# Beacon_V1.net
KiCad netlist of a schematic drawn in Altium Designer
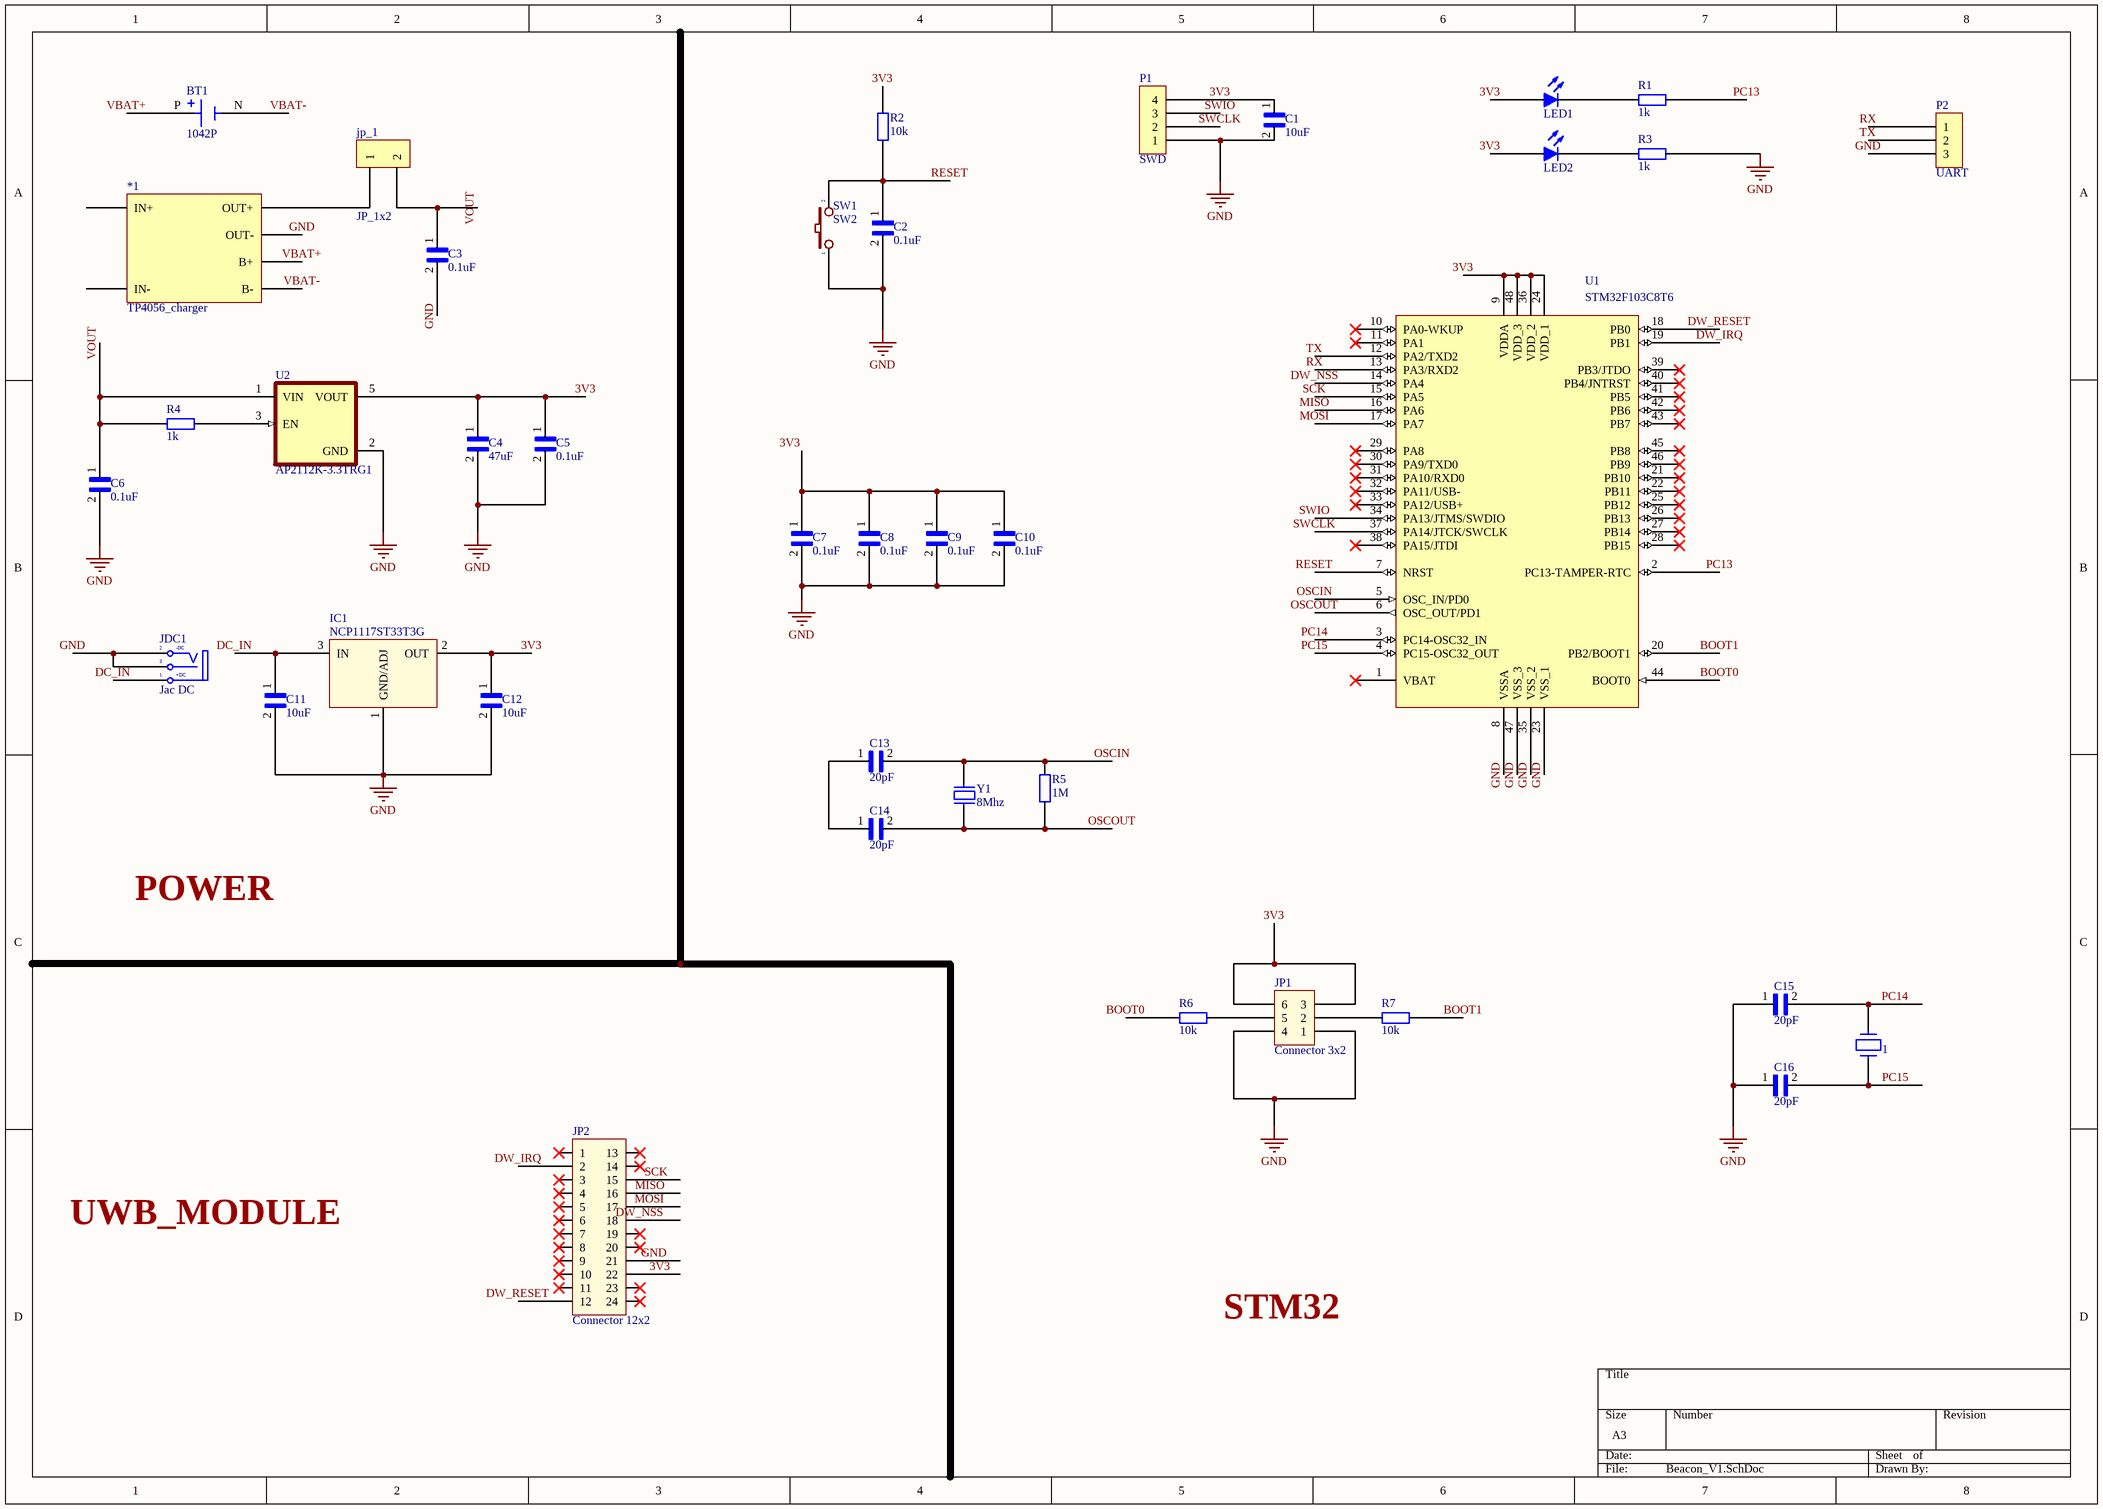
[diagram p0: Beacon_V1.SchDoc]

(export (version "E")
  (design (tool "Eeschema 10.0.6"))
  (components
    (comp (ref "*1")
      (value "TP4056_charger")
      (footprint "TP4056_charger")
      (libsource (lib "Target_tracking_20242v3") (part "TP4056_charger"))
    )
    (comp (ref "1")
      (value "ABS07")
      (footprint "ABS07")
      (description "SMD Quartz Crystal")
      (fields (field (name "CREATED BY") "Zion Blue") (field (name "PUBLISHER") "Cynetik Group"))
      (libsource (lib "Cty1") (part "ABS07"))
    )
    (comp (ref "BT1")
      (value "1042P")
      (footprint "BAT_1042P")
      (description "SMT Polarized Battery Holder for 18650 Battery ¦ Keystone Electronics 1042P")
      (fields (field (name "MF") "Keystone Electronics"))
      (libsource (lib "Project_LoRa") (part "1042P"))
    )
    (comp (ref "C1")
      (value "10uF")
      (footprint "Capacitor_0805")
      (description "Capacitor; Ceramic; Cap; .220uF; Tol 10%; SMT; Vol-Rtg 50V; X7R; Tape And Reel")
      (libsource (lib "") (part "Capacitor_0805_1"))
    )
    (comp (ref "C2")
      (value "0.1uF")
      (footprint "Capacitor_0805")
      (description "Capacitor; Ceramic; Cap; .220uF; Tol 10%; SMT; Vol-Rtg 50V; X7R; Tape And Reel")
      (libsource (lib "") (part "Capacitor_0805_1"))
    )
    (comp (ref "C3")
      (value "0.1uF")
      (footprint "Capacitor_0805")
      (description "Capacitor; Ceramic; Cap; .220uF; Tol 10%; SMT; Vol-Rtg 50V; X7R; Tape And Reel")
      (libsource (lib "") (part "Capacitor_0805_1"))
    )
    (comp (ref "C4")
      (value "47uF")
      (footprint "Capacitor_0805")
      (description "Capacitor; Ceramic; Cap; .220uF; Tol 10%; SMT; Vol-Rtg 50V; X7R; Tape And Reel")
      (libsource (lib "") (part "Capacitor_0805_1"))
    )
    (comp (ref "C5")
      (value "0.1uF")
      (footprint "Capacitor_0805")
      (description "Capacitor; Ceramic; Cap; .220uF; Tol 10%; SMT; Vol-Rtg 50V; X7R; Tape And Reel")
      (libsource (lib "") (part "Capacitor_0805_1"))
    )
    (comp (ref "C6")
      (value "0.1uF")
      (footprint "Capacitor_0805")
      (description "Capacitor; Ceramic; Cap; .220uF; Tol 10%; SMT; Vol-Rtg 50V; X7R; Tape And Reel")
      (libsource (lib "") (part "Capacitor_0805_1"))
    )
    (comp (ref "C7")
      (value "0.1uF")
      (footprint "Capacitor_0805")
      (description "Capacitor; Ceramic; Cap; .220uF; Tol 10%; SMT; Vol-Rtg 50V; X7R; Tape And Reel")
      (libsource (lib "") (part "Capacitor_0805_1"))
    )
    (comp (ref "C8")
      (value "0.1uF")
      (footprint "Capacitor_0805")
      (description "Capacitor; Ceramic; Cap; .220uF; Tol 10%; SMT; Vol-Rtg 50V; X7R; Tape And Reel")
      (libsource (lib "") (part "Capacitor_0805_1"))
    )
    (comp (ref "C9")
      (value "0.1uF")
      (footprint "Capacitor_0805")
      (description "Capacitor; Ceramic; Cap; .220uF; Tol 10%; SMT; Vol-Rtg 50V; X7R; Tape And Reel")
      (libsource (lib "") (part "Capacitor_0805_1"))
    )
    (comp (ref "C10")
      (value "0.1uF")
      (footprint "Capacitor_0805")
      (description "Capacitor; Ceramic; Cap; .220uF; Tol 10%; SMT; Vol-Rtg 50V; X7R; Tape And Reel")
      (libsource (lib "") (part "Capacitor_0805_1"))
    )
    (comp (ref "C11")
      (value "10uF")
      (footprint "Capacitor_0805")
      (description "Capacitor; Ceramic; Cap; .220uF; Tol 10%; SMT; Vol-Rtg 50V; X7R; Tape And Reel")
      (libsource (lib "") (part "Capacitor_0805_1"))
    )
    (comp (ref "C12")
      (value "10uF")
      (footprint "Capacitor_0805")
      (description "Capacitor; Ceramic; Cap; .220uF; Tol 10%; SMT; Vol-Rtg 50V; X7R; Tape And Reel")
      (libsource (lib "") (part "Capacitor_0805_1"))
    )
    (comp (ref "C13")
      (value "20pF")
      (footprint "Capacitor_0805")
      (description "Capacitor; Ceramic; Cap; .220uF; Tol 10%; SMT; Vol-Rtg 50V; X7R; Tape And Reel")
      (libsource (lib "Target_tracking_20242v3") (part "Capacitor_0805"))
    )
    (comp (ref "C14")
      (value "20pF")
      (footprint "Capacitor_0805")
      (description "Capacitor; Ceramic; Cap; .220uF; Tol 10%; SMT; Vol-Rtg 50V; X7R; Tape And Reel")
      (libsource (lib "Target_tracking_20242v3") (part "Capacitor_0805"))
    )
    (comp (ref "C15")
      (value "20pF")
      (footprint "Capacitor_0805")
      (description "Capacitor; Ceramic; Cap; .220uF; Tol 10%; SMT; Vol-Rtg 50V; X7R; Tape And Reel")
      (libsource (lib "Target_tracking_20242v3") (part "Capacitor_0805"))
    )
    (comp (ref "C16")
      (value "20pF")
      (footprint "Capacitor_0805")
      (description "Capacitor; Ceramic; Cap; .220uF; Tol 10%; SMT; Vol-Rtg 50V; X7R; Tape And Reel")
      (libsource (lib "Target_tracking_20242v3") (part "Capacitor_0805"))
    )
    (comp (ref "IC1")
      (value "NCP1117ST33T3G")
      (footprint "SOT223-3_ONS")
      (description "SOT223")
      (libsource (lib "SCH_MyLib_0") (part "NCP1117ST33T3G"))
    )
    (comp (ref "JDC1")
      (value "Jac DC")
      (footprint "DC-IN")
      (description "Jac DC input")
      (libsource (lib "syhaunguyen") (part "DCIN"))
    )
    (comp (ref "JP1") (value "Connector 3x2") (footprint "JP3x2") (libsource (lib "Cty1") (part "JP3x2")))
    (comp (ref "JP2")
      (value "Connector 12x2")
      (footprint "JP12X2_1")
      (libsource (lib "Cty1") (part "JP12x2"))
    )
    (comp (ref "jp_1")
      (value "JP_1x2")
      (footprint "JP_1x2")
      (libsource (lib "Target_tracking_20242v3") (part "JP_1x2"))
    )
    (comp (ref "LED1")
      (value "Led")
      (footprint "Led 0805 Blue")
      (description "Typical LED")
      (libsource (lib "Project_LoRa") (part "Led"))
    )
    (comp (ref "LED2")
      (value "Led")
      (footprint "Led 0805 Blue")
      (description "Typical LED")
      (libsource (lib "Project_LoRa") (part "Led"))
    )
    (comp (ref "P1")
      (value "SWD")
      (footprint "HDR/Header/4/BOX")
      (description "Header, 4-Pin")
      (libsource (lib "Project_LoRa") (part "Header 4_1"))
    )
    (comp (ref "P2")
      (value "UART")
      (footprint "HDR/Header/3/BOX")
      (description "Header, 3-Pin")
      (libsource (lib "Project_LoRa") (part "Header 3"))
    )
    (comp (ref "R1")
      (value "1k")
      (footprint "tro smd 0805")
      (description "Dán")
      (libsource (lib "Project_LoRa") (part "Tro 0805 1% 1k"))
    )
    (comp (ref "R2")
      (value "10k")
      (footprint "tro smd 0805")
      (description "Dán")
      (libsource (lib "Project_LoRa") (part "Tro 0805 1% 10k"))
    )
    (comp (ref "R3")
      (value "1k")
      (footprint "tro smd 0805")
      (description "Dán")
      (libsource (lib "Project_LoRa") (part "Tro 0805 1% 1k"))
    )
    (comp (ref "R4")
      (value "1k")
      (footprint "tro smd 0805")
      (description "Dán")
      (libsource (lib "Project_LoRa") (part "Tro 0805 1% 1k"))
    )
    (comp (ref "R5")
      (value "1M")
      (footprint "tro smd 0805")
      (description "Dán")
      (libsource (lib "Project_LoRa") (part "Tro 0805 1% 1M"))
    )
    (comp (ref "R6")
      (value "10k")
      (footprint "tro smd 0805")
      (description "Dán")
      (libsource (lib "Project_LoRa") (part "Tro 0805 1% 10k"))
    )
    (comp (ref "R7")
      (value "10k")
      (footprint "tro smd 0805")
      (description "Dán")
      (libsource (lib "Project_LoRa") (part "Tro 0805 1% 10k"))
    )
    (comp (ref "SW1")
      (value "SW2")
      (footprint "SW1-SMD")
      (description "Switch button 2 pin")
      (libsource (lib "Project_LoRa") (part "SW2"))
    )
    (comp (ref "U1")
      (value "STM32F103C8T6")
      (footprint "LQFP48")
      (fields (field (name "PUBLISHER") "Altium Limited"))
      (libsource (lib "Project_LoRa") (part "STM32F103C8T6"))
    )
    (comp (ref "U2")
      (value "AP2112K-3.3TRG1")
      (footprint "SOT95P285X140-5N")
      (description "Linear Voltage Regulator IC Positive Fixed 1 Output 600mA SOT-25")
      (fields (field (name "MF") "Diodes Inc."))
      (libsource (lib "Project_LoRa") (part "AP2112K-3.3TRG1"))
    )
    (comp (ref "Y1")
      (value "8Mhz")
      (footprint "Thach Anh 2 chan SMD5032")
      (description "Crystal For all Crystal 2pin.")
      (libsource (lib "Project_LoRa") (part "Thach Anh 2 chan SMD 5032"))
    )
  )
  (nets
    (net (code "1") (name "/3V3") (class "Default")
      (node (ref "C1") (pin "1") (pinfunction "1_1") (pintype "passive"))
      (node (ref "C10") (pin "1") (pinfunction "1_1") (pintype "passive"))
      (node (ref "C12") (pin "1") (pinfunction "1_1") (pintype "passive"))
      (node (ref "C4") (pin "1") (pinfunction "1_1") (pintype "passive"))
      (node (ref "C5") (pin "1") (pinfunction "1_1") (pintype "passive"))
      (node (ref "C7") (pin "1") (pinfunction "1_1") (pintype "passive"))
      (node (ref "C8") (pin "1") (pinfunction "1_1") (pintype "passive"))
      (node (ref "C9") (pin "1") (pinfunction "1_1") (pintype "passive"))
      (node (ref "IC1") (pin "2") (pinfunction "OUT_2") (pintype "passive"))
      (node (ref "JP1") (pin "3") (pinfunction "3_3") (pintype "passive"))
      (node (ref "JP1") (pin "6") (pinfunction "6_6") (pintype "passive"))
      (node (ref "JP2") (pin "22") (pinfunction "22_22") (pintype "passive"))
      (node (ref "LED1") (pin "1") (pinfunction "A_1") (pintype "passive"))
      (node (ref "LED2") (pin "1") (pinfunction "A_1") (pintype "passive"))
      (node (ref "P1") (pin "4") (pinfunction "4_4") (pintype "passive"))
      (node (ref "R2") (pin "2") (pinfunction "2_2") (pintype "passive"))
      (node (ref "U1") (pin "24") (pinfunction "VDD_1_24") (pintype "power_in"))
      (node (ref "U1") (pin "36") (pinfunction "VDD_2_36") (pintype "power_in"))
      (node (ref "U1") (pin "48") (pinfunction "VDD_3_48") (pintype "power_in"))
      (node (ref "U1") (pin "9") (pinfunction "VDDA_9") (pintype "power_in"))
      (node (ref "U2") (pin "5") (pinfunction "VOUT_5") (pintype "power_in"))
    )
    (net (code "2") (name "/BOOT0") (class "Default")
      (node (ref "R6") (pin "1") (pinfunction "1_1") (pintype "passive"))
      (node (ref "U1") (pin "44") (pinfunction "BOOT0_44") (pintype "input"))
    )
    (net (code "3") (name "/BOOT1") (class "Default")
      (node (ref "R7") (pin "2") (pinfunction "2_2") (pintype "passive"))
      (node (ref "U1") (pin "20") (pinfunction "PB2/BOOT1_20") (pintype "bidirectional"))
    )
    (net (code "4") (name "/DC_IN") (class "Default")
      (node (ref "C11") (pin "1") (pinfunction "1_1") (pintype "passive"))
      (node (ref "IC1") (pin "3") (pinfunction "IN_3") (pintype "passive"))
      (node (ref "JDC1") (pin "1") (pinfunction "T_1") (pintype "passive"))
    )
    (net (code "5") (name "/DW_IRQ") (class "Default")
      (node (ref "JP2") (pin "2") (pinfunction "2_2") (pintype "passive"))
      (node (ref "U1") (pin "19") (pinfunction "PB1_19") (pintype "bidirectional"))
    )
    (net (code "6") (name "/DW_NSS") (class "Default")
      (node (ref "JP2") (pin "18") (pinfunction "18_18") (pintype "passive"))
      (node (ref "U1") (pin "14") (pinfunction "PA4_14") (pintype "bidirectional"))
    )
    (net (code "7") (name "/DW_RESET") (class "Default")
      (node (ref "JP2") (pin "12") (pinfunction "12_12") (pintype "passive"))
      (node (ref "U1") (pin "18") (pinfunction "PB0_18") (pintype "bidirectional"))
    )
    (net (code "8") (name "/MISO") (class "Default")
      (node (ref "JP2") (pin "16") (pinfunction "16_16") (pintype "passive"))
      (node (ref "U1") (pin "16") (pinfunction "PA6_16") (pintype "bidirectional"))
    )
    (net (code "9") (name "/MOSI") (class "Default")
      (node (ref "JP2") (pin "17") (pinfunction "17_17") (pintype "passive"))
      (node (ref "U1") (pin "17") (pinfunction "PA7_17") (pintype "bidirectional"))
    )
    (net (code "10") (name "/OSCIN") (class "Default")
      (node (ref "C13") (pin "2") (pinfunction "2_2") (pintype "passive"))
      (node (ref "R5") (pin "2") (pinfunction "2_2") (pintype "passive"))
      (node (ref "U1") (pin "5") (pinfunction "OSC_IN/PD0_5") (pintype "input"))
      (node (ref "Y1") (pin "2") (pinfunction "2_2") (pintype "passive"))
    )
    (net (code "11") (name "/OSCOUT") (class "Default")
      (node (ref "C14") (pin "2") (pinfunction "2_2") (pintype "passive"))
      (node (ref "R5") (pin "1") (pinfunction "1_1") (pintype "passive"))
      (node (ref "U1") (pin "6") (pinfunction "OSC_OUT/PD1_6") (pintype "output"))
      (node (ref "Y1") (pin "1") (pinfunction "1_1") (pintype "passive"))
    )
    (net (code "12") (name "/PC13") (class "Default")
      (node (ref "R1") (pin "2") (pinfunction "2_2") (pintype "passive"))
      (node (ref "U1") (pin "2") (pinfunction "PC13-TAMPER-RTC_2") (pintype "bidirectional"))
    )
    (net (code "13") (name "/PC14") (class "Default")
      (node (ref "1") (pin "2") (pinfunction "2_2") (pintype "passive"))
      (node (ref "C15") (pin "2") (pinfunction "2_2") (pintype "passive"))
      (node (ref "U1") (pin "3") (pinfunction "PC14-OSC32_IN_3") (pintype "bidirectional"))
    )
    (net (code "14") (name "/PC15") (class "Default")
      (node (ref "1") (pin "1") (pinfunction "1_1") (pintype "passive"))
      (node (ref "C16") (pin "2") (pinfunction "2_2") (pintype "passive"))
      (node (ref "U1") (pin "4") (pinfunction "PC15-OSC32_OUT_4") (pintype "bidirectional"))
    )
    (net (code "15") (name "/RESET") (class "Default")
      (node (ref "C2") (pin "1") (pinfunction "1_1") (pintype "passive"))
      (node (ref "R2") (pin "1") (pinfunction "1_1") (pintype "passive"))
      (node (ref "SW1") (pin "2") (pinfunction "2_2") (pintype "passive"))
      (node (ref "U1") (pin "7") (pinfunction "NRST_7") (pintype "bidirectional"))
    )
    (net (code "16") (name "/RX") (class "Default")
      (node (ref "P2") (pin "1") (pinfunction "1_1") (pintype "passive"))
      (node (ref "U1") (pin "13") (pinfunction "PA3/RXD2_13") (pintype "bidirectional"))
    )
    (net (code "17") (name "/SCK") (class "Default")
      (node (ref "JP2") (pin "15") (pinfunction "15_15") (pintype "passive"))
      (node (ref "U1") (pin "15") (pinfunction "PA5_15") (pintype "bidirectional"))
    )
    (net (code "18") (name "/SWCLK") (class "Default")
      (node (ref "P1") (pin "2") (pinfunction "2_2") (pintype "passive"))
      (node (ref "U1") (pin "37") (pinfunction "PA14/JTCK/SWCLK_37") (pintype "bidirectional"))
    )
    (net (code "19") (name "/SWIO") (class "Default")
      (node (ref "P1") (pin "3") (pinfunction "3_3") (pintype "passive"))
      (node (ref "U1") (pin "34") (pinfunction "PA13/JTMS/SWDIO_34") (pintype "bidirectional"))
    )
    (net (code "20") (name "/TX") (class "Default")
      (node (ref "P2") (pin "2") (pinfunction "2_2") (pintype "passive"))
      (node (ref "U1") (pin "12") (pinfunction "PA2/TXD2_12") (pintype "bidirectional"))
    )
    (net (code "21") (name "/VBAT+") (class "Default")
      (node (ref "*1") (pin "1") (pinfunction "B+_1") (pintype "passive"))
      (node (ref "BT1") (pin "P") (pinfunction "POS_P") (pintype "passive"))
    )
    (net (code "22") (name "/VBAT-") (class "Default")
      (node (ref "*1") (pin "2") (pinfunction "B-_2") (pintype "passive"))
      (node (ref "BT1") (pin "N") (pinfunction "NEG_N") (pintype "passive"))
    )
    (net (code "23") (name "/VOUT") (class "Default")
      (node (ref "C3") (pin "1") (pinfunction "1_1") (pintype "passive"))
      (node (ref "C6") (pin "1") (pinfunction "1_1") (pintype "passive"))
      (node (ref "R4") (pin "1") (pinfunction "1_1") (pintype "passive"))
      (node (ref "U2") (pin "1") (pinfunction "VIN_1") (pintype "power_in"))
      (node (ref "jp_1") (pin "2") (pinfunction "2_2") (pintype "passive"))
    )
    (net (code "24") (name "GND") (class "Default")
      (node (ref "*1") (pin "4") (pinfunction "OUT-_4") (pintype "passive"))
      (node (ref "C1") (pin "2") (pinfunction "2_2") (pintype "passive"))
      (node (ref "C10") (pin "2") (pinfunction "2_2") (pintype "passive"))
      (node (ref "C11") (pin "2") (pinfunction "2_2") (pintype "passive"))
      (node (ref "C12") (pin "2") (pinfunction "2_2") (pintype "passive"))
      (node (ref "C15") (pin "1") (pinfunction "1_1") (pintype "passive"))
      (node (ref "C16") (pin "1") (pinfunction "1_1") (pintype "passive"))
      (node (ref "C2") (pin "2") (pinfunction "2_2") (pintype "passive"))
      (node (ref "C3") (pin "2") (pinfunction "2_2") (pintype "passive"))
      (node (ref "C4") (pin "2") (pinfunction "2_2") (pintype "passive"))
      (node (ref "C5") (pin "2") (pinfunction "2_2") (pintype "passive"))
      (node (ref "C6") (pin "2") (pinfunction "2_2") (pintype "passive"))
      (node (ref "C7") (pin "2") (pinfunction "2_2") (pintype "passive"))
      (node (ref "C8") (pin "2") (pinfunction "2_2") (pintype "passive"))
      (node (ref "C9") (pin "2") (pinfunction "2_2") (pintype "passive"))
      (node (ref "IC1") (pin "1") (pinfunction "GND/ADJ_1") (pintype "passive"))
      (node (ref "JDC1") (pin "2") (pinfunction "TN_2") (pintype "passive"))
      (node (ref "JDC1") (pin "3") (pinfunction "S_3") (pintype "power_in"))
      (node (ref "JP1") (pin "1") (pinfunction "1_1") (pintype "passive"))
      (node (ref "JP1") (pin "4") (pinfunction "4_4") (pintype "passive"))
      (node (ref "JP2") (pin "21") (pinfunction "21_21") (pintype "passive"))
      (node (ref "P1") (pin "1") (pinfunction "1_1") (pintype "passive"))
      (node (ref "P2") (pin "3") (pinfunction "3_3") (pintype "passive"))
      (node (ref "R3") (pin "2") (pinfunction "2_2") (pintype "passive"))
      (node (ref "SW1") (pin "1") (pinfunction "1_1") (pintype "passive"))
      (node (ref "U1") (pin "23") (pinfunction "VSS_1_23") (pintype "power_in"))
      (node (ref "U1") (pin "35") (pinfunction "VSS_2_35") (pintype "power_in"))
      (node (ref "U1") (pin "47") (pinfunction "VSS_3_47") (pintype "power_in"))
      (node (ref "U1") (pin "8") (pinfunction "VSSA_8") (pintype "power_in"))
      (node (ref "U2") (pin "2") (pinfunction "GND_2") (pintype "power_in"))
    )
    (net (code "25") (name "Net-(*1-OUT+)") (class "Default")
      (node (ref "*1") (pin "3") (pinfunction "OUT+_3") (pintype "passive"))
      (node (ref "jp_1") (pin "1") (pinfunction "1_1") (pintype "passive"))
    )
    (net (code "26") (name "Net-(C13-Pad1)") (class "Default")
      (node (ref "C13") (pin "1") (pinfunction "1_1") (pintype "passive"))
      (node (ref "C14") (pin "1") (pinfunction "1_1") (pintype "passive"))
    )
    (net (code "27") (name "Net-(JP1-Pad2)") (class "Default")
      (node (ref "JP1") (pin "2") (pinfunction "2_2") (pintype "passive"))
      (node (ref "R7") (pin "1") (pinfunction "1_1") (pintype "passive"))
    )
    (net (code "28") (name "Net-(JP1-Pad5)") (class "Default")
      (node (ref "JP1") (pin "5") (pinfunction "5_5") (pintype "passive"))
      (node (ref "R6") (pin "2") (pinfunction "2_2") (pintype "passive"))
    )
    (net (code "29") (name "Net-(LED1-K)") (class "Default")
      (node (ref "LED1") (pin "2") (pinfunction "K_2") (pintype "passive"))
      (node (ref "R1") (pin "1") (pinfunction "1_1") (pintype "passive"))
    )
    (net (code "30") (name "Net-(LED2-K)") (class "Default")
      (node (ref "LED2") (pin "2") (pinfunction "K_2") (pintype "passive"))
      (node (ref "R3") (pin "1") (pinfunction "1_1") (pintype "passive"))
    )
    (net (code "31") (name "Net-(U2-EN)") (class "Default")
      (node (ref "R4") (pin "2") (pinfunction "2_2") (pintype "passive"))
      (node (ref "U2") (pin "3") (pinfunction "EN_3") (pintype "input"))
    )
    (net (code "32") (name "unconnected-(*1-IN+-Pad5)") (class "Default")
      (node (ref "*1") (pin "5") (pinfunction "IN+_5") (pintype "passive"))
    )
    (net (code "33") (name "unconnected-(*1-IN--Pad6)") (class "Default")
      (node (ref "*1") (pin "6") (pinfunction "IN-_6") (pintype "passive"))
    )
    (net (code "34") (name "unconnected-(JP2-Pad1)") (class "Default")
      (node (ref "JP2") (pin "1") (pinfunction "1_1") (pintype "passive+no_connect"))
    )
    (net (code "35") (name "unconnected-(JP2-Pad3)") (class "Default")
      (node (ref "JP2") (pin "3") (pinfunction "3_3") (pintype "passive+no_connect"))
    )
    (net (code "36") (name "unconnected-(JP2-Pad4)") (class "Default")
      (node (ref "JP2") (pin "4") (pinfunction "4_4") (pintype "passive+no_connect"))
    )
    (net (code "37") (name "unconnected-(JP2-Pad5)") (class "Default")
      (node (ref "JP2") (pin "5") (pinfunction "5_5") (pintype "passive+no_connect"))
    )
    (net (code "38") (name "unconnected-(JP2-Pad6)") (class "Default")
      (node (ref "JP2") (pin "6") (pinfunction "6_6") (pintype "passive+no_connect"))
    )
    (net (code "39") (name "unconnected-(JP2-Pad7)") (class "Default")
      (node (ref "JP2") (pin "7") (pinfunction "7_7") (pintype "passive+no_connect"))
    )
    (net (code "40") (name "unconnected-(JP2-Pad8)") (class "Default")
      (node (ref "JP2") (pin "8") (pinfunction "8_8") (pintype "passive+no_connect"))
    )
    (net (code "41") (name "unconnected-(JP2-Pad9)") (class "Default")
      (node (ref "JP2") (pin "9") (pinfunction "9_9") (pintype "passive+no_connect"))
    )
    (net (code "42") (name "unconnected-(JP2-Pad10)") (class "Default")
      (node (ref "JP2") (pin "10") (pinfunction "10_10") (pintype "passive+no_connect"))
    )
    (net (code "43") (name "unconnected-(JP2-Pad11)") (class "Default")
      (node (ref "JP2") (pin "11") (pinfunction "11_11") (pintype "passive+no_connect"))
    )
    (net (code "44") (name "unconnected-(JP2-Pad13)") (class "Default")
      (node (ref "JP2") (pin "13") (pinfunction "13_13") (pintype "passive+no_connect"))
    )
    (net (code "45") (name "unconnected-(JP2-Pad14)") (class "Default")
      (node (ref "JP2") (pin "14") (pinfunction "14_14") (pintype "passive+no_connect"))
    )
    (net (code "46") (name "unconnected-(JP2-Pad19)") (class "Default")
      (node (ref "JP2") (pin "19") (pinfunction "19_19") (pintype "passive+no_connect"))
    )
    (net (code "47") (name "unconnected-(JP2-Pad20)") (class "Default")
      (node (ref "JP2") (pin "20") (pinfunction "20_20") (pintype "passive+no_connect"))
    )
    (net (code "48") (name "unconnected-(JP2-Pad23)") (class "Default")
      (node (ref "JP2") (pin "23") (pinfunction "23_23") (pintype "passive+no_connect"))
    )
    (net (code "49") (name "unconnected-(JP2-Pad24)") (class "Default")
      (node (ref "JP2") (pin "24") (pinfunction "24_24") (pintype "passive+no_connect"))
    )
    (net (code "50") (name "unconnected-(U1-PA0-WKUP-Pad10)") (class "Default")
      (node (ref "U1") (pin "10") (pinfunction "PA0-WKUP_10") (pintype "bidirectional+no_connect"))
    )
    (net (code "51") (name "unconnected-(U1-PA1-Pad11)") (class "Default")
      (node (ref "U1") (pin "11") (pinfunction "PA1_11") (pintype "bidirectional+no_connect"))
    )
    (net (code "52") (name "unconnected-(U1-PA8-Pad29)") (class "Default")
      (node (ref "U1") (pin "29") (pinfunction "PA8_29") (pintype "bidirectional+no_connect"))
    )
    (net (code "53") (name "unconnected-(U1-PA9{slash}TXD0-Pad30)") (class "Default")
      (node (ref "U1") (pin "30") (pinfunction "PA9/TXD0_30") (pintype "bidirectional+no_connect"))
    )
    (net (code "54") (name "unconnected-(U1-PA10{slash}RXD0-Pad31)") (class "Default")
      (node (ref "U1") (pin "31") (pinfunction "PA10/RXD0_31") (pintype "bidirectional+no_connect"))
    )
    (net (code "55") (name "unconnected-(U1-PA11{slash}USB--Pad32)") (class "Default")
      (node (ref "U1") (pin "32") (pinfunction "PA11/USB-_32") (pintype "bidirectional+no_connect"))
    )
    (net (code "56") (name "unconnected-(U1-PA12{slash}USB+-Pad33)") (class "Default")
      (node (ref "U1") (pin "33") (pinfunction "PA12/USB+_33") (pintype "bidirectional+no_connect"))
    )
    (net (code "57") (name "unconnected-(U1-PA15{slash}JTDI-Pad38)") (class "Default")
      (node (ref "U1") (pin "38") (pinfunction "PA15/JTDI_38") (pintype "bidirectional+no_connect"))
    )
    (net (code "58") (name "unconnected-(U1-PB3{slash}JTDO-Pad39)") (class "Default")
      (node (ref "U1") (pin "39") (pinfunction "PB3/JTDO_39") (pintype "bidirectional+no_connect"))
    )
    (net (code "59") (name "unconnected-(U1-PB4{slash}JNTRST-Pad40)") (class "Default")
      (node (ref "U1") (pin "40") (pinfunction "PB4/JNTRST_40") (pintype "bidirectional+no_connect"))
    )
    (net (code "60") (name "unconnected-(U1-PB5-Pad41)") (class "Default")
      (node (ref "U1") (pin "41") (pinfunction "PB5_41") (pintype "bidirectional+no_connect"))
    )
    (net (code "61") (name "unconnected-(U1-PB6-Pad42)") (class "Default")
      (node (ref "U1") (pin "42") (pinfunction "PB6_42") (pintype "bidirectional+no_connect"))
    )
    (net (code "62") (name "unconnected-(U1-PB7-Pad43)") (class "Default")
      (node (ref "U1") (pin "43") (pinfunction "PB7_43") (pintype "bidirectional+no_connect"))
    )
    (net (code "63") (name "unconnected-(U1-PB8-Pad45)") (class "Default")
      (node (ref "U1") (pin "45") (pinfunction "PB8_45") (pintype "bidirectional+no_connect"))
    )
    (net (code "64") (name "unconnected-(U1-PB9-Pad46)") (class "Default")
      (node (ref "U1") (pin "46") (pinfunction "PB9_46") (pintype "bidirectional+no_connect"))
    )
    (net (code "65") (name "unconnected-(U1-PB10-Pad21)") (class "Default")
      (node (ref "U1") (pin "21") (pinfunction "PB10_21") (pintype "bidirectional+no_connect"))
    )
    (net (code "66") (name "unconnected-(U1-PB11-Pad22)") (class "Default")
      (node (ref "U1") (pin "22") (pinfunction "PB11_22") (pintype "bidirectional+no_connect"))
    )
    (net (code "67") (name "unconnected-(U1-PB12-Pad25)") (class "Default")
      (node (ref "U1") (pin "25") (pinfunction "PB12_25") (pintype "bidirectional+no_connect"))
    )
    (net (code "68") (name "unconnected-(U1-PB13-Pad26)") (class "Default")
      (node (ref "U1") (pin "26") (pinfunction "PB13_26") (pintype "bidirectional+no_connect"))
    )
    (net (code "69") (name "unconnected-(U1-PB14-Pad27)") (class "Default")
      (node (ref "U1") (pin "27") (pinfunction "PB14_27") (pintype "bidirectional+no_connect"))
    )
    (net (code "70") (name "unconnected-(U1-PB15-Pad28)") (class "Default")
      (node (ref "U1") (pin "28") (pinfunction "PB15_28") (pintype "bidirectional+no_connect"))
    )
    (net (code "71") (name "unconnected-(U1-VBAT-Pad1)") (class "Default")
      (node (ref "U1") (pin "1") (pinfunction "VBAT_1") (pintype "power_in+no_connect"))
    )
  )
)
